# Strain-Maxim.net
KiCad netlist of a schematic drawn in Altium Designer
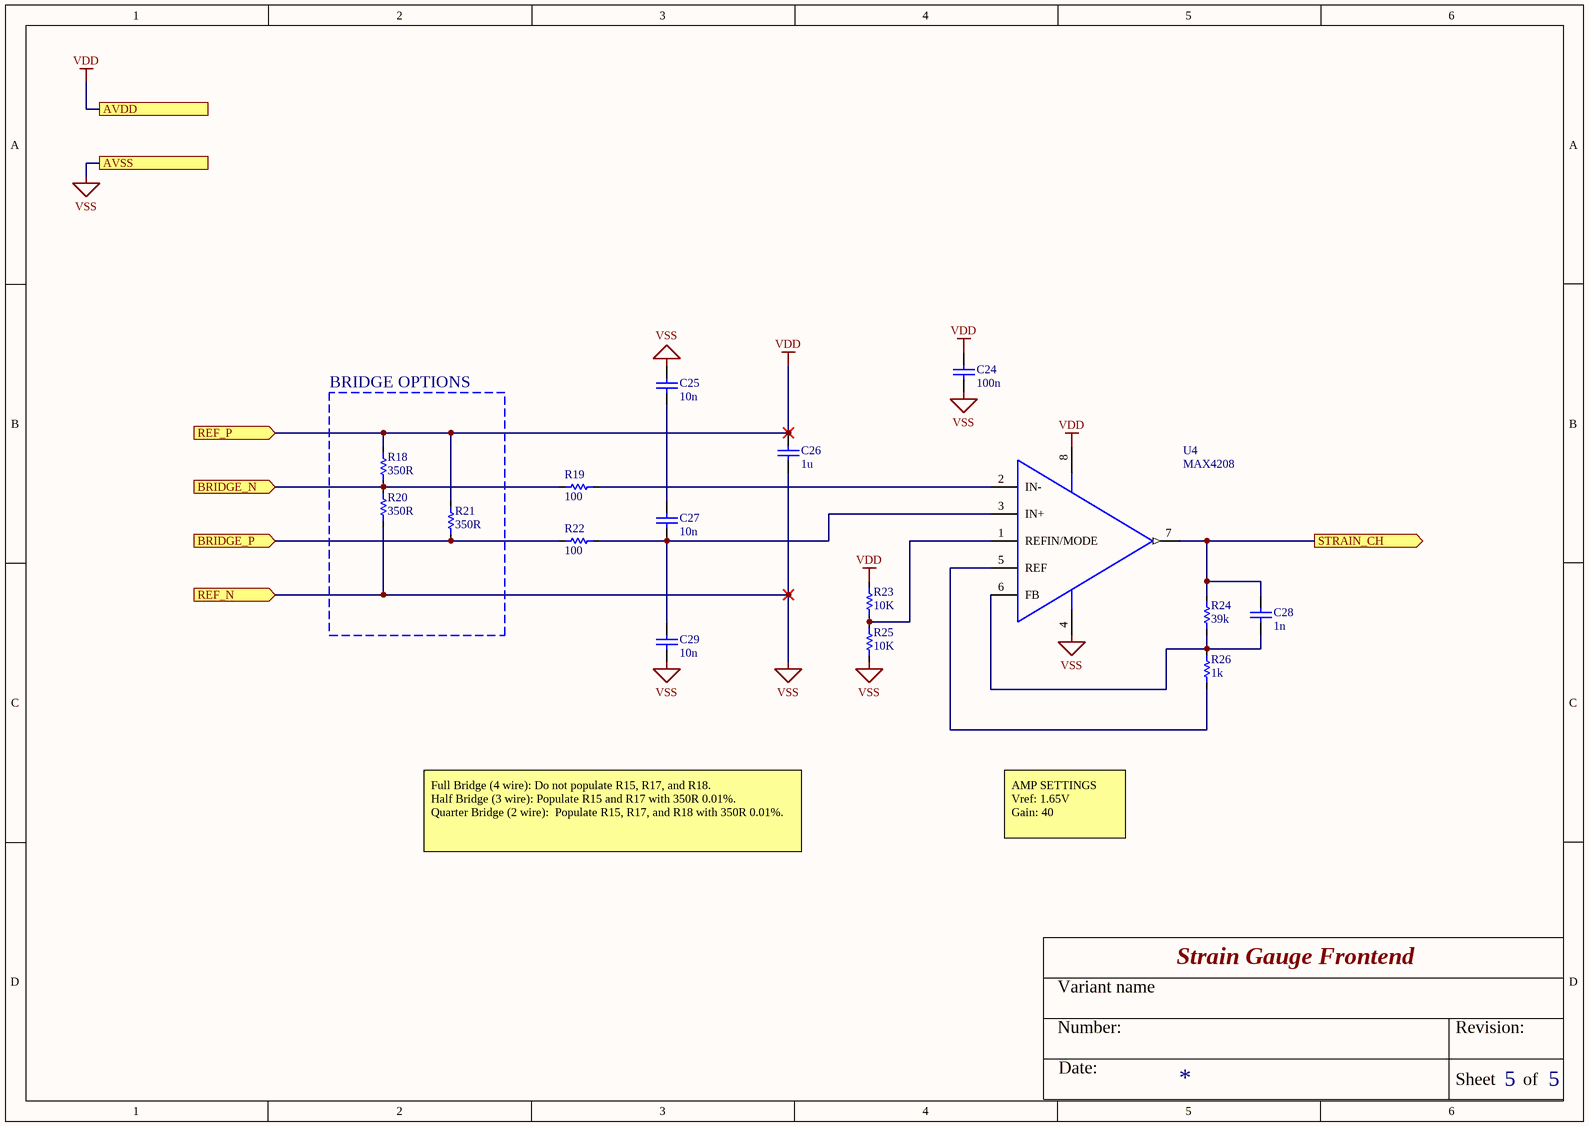
[diagram p0: Strain-Maxim.SchDoc]

(export (version "E")
  (design (tool "Eeschema 10.0.6"))
  (components
    (comp (ref "C24")
      (value "100n")
      (footprint "CAP_0603_M")
      (description "CAP Cnom Vcap Ptol Dial 0603")
      (fields (field (name "CREATED BY") "JS"))
      (libsource (lib "Passives") (part "CAP_0603"))
    )
    (comp (ref "C25")
      (value "10n")
      (footprint "CAP_0603_M")
      (description "CAP Cnom Vcap Ptol Dial 0603")
      (fields (field (name "CREATED BY") "JS"))
      (libsource (lib "Passives") (part "CAP_0603"))
    )
    (comp (ref "C26")
      (value "1u")
      (footprint "CAP_0603_M")
      (description "CAP Cnom Vcap Ptol Dial 0603")
      (fields (field (name "CREATED BY") "JS"))
      (libsource (lib "Passives") (part "CAP_0603"))
    )
    (comp (ref "C27")
      (value "10n")
      (footprint "CAP_0603_M")
      (description "CAP Cnom Vcap Ptol Dial 0603")
      (fields (field (name "CREATED BY") "JS"))
      (libsource (lib "Passives") (part "CAP_0603"))
    )
    (comp (ref "C28")
      (value "1n")
      (footprint "CAP_0603_M")
      (description "CAP Cnom Vcap Ptol Dial 0603")
      (fields (field (name "CREATED BY") "JS"))
      (libsource (lib "Passives") (part "CAP_0603"))
    )
    (comp (ref "C29")
      (value "10n")
      (footprint "CAP_0603_M")
      (description "CAP Cnom Vcap Ptol Dial 0603")
      (fields (field (name "CREATED BY") "JS"))
      (libsource (lib "Passives") (part "CAP_0603"))
    )
    (comp (ref "R18")
      (value "350R")
      (footprint "RES_0603_M")
      (description "RES OPT 1/5W 0603")
      (fields (field (name "CREATED BY") "JS"))
      (libsource (lib "Passives") (part "RES_0603"))
    )
    (comp (ref "R19")
      (value "100")
      (footprint "RES_0603_M")
      (description "RES OPT 1/5W 0603")
      (fields (field (name "CREATED BY") "JS"))
      (libsource (lib "Passives") (part "RES_0603"))
    )
    (comp (ref "R20")
      (value "350R")
      (footprint "RES_0603_M")
      (description "RES OPT 1/5W 0603")
      (fields (field (name "CREATED BY") "JS"))
      (libsource (lib "Passives") (part "RES_0603"))
    )
    (comp (ref "R21")
      (value "350R")
      (footprint "RES_0603_M")
      (description "RES OPT 1/5W 0603")
      (fields (field (name "CREATED BY") "JS"))
      (libsource (lib "Passives") (part "RES_0603"))
    )
    (comp (ref "R22")
      (value "100")
      (footprint "RES_0603_M")
      (description "RES OPT 1/5W 0603")
      (fields (field (name "CREATED BY") "JS"))
      (libsource (lib "Passives") (part "RES_0603"))
    )
    (comp (ref "R23")
      (value "10K")
      (footprint "RES_0603_M")
      (description "RES OPT 1/5W 0603")
      (fields (field (name "CREATED BY") "JS"))
      (libsource (lib "Passives") (part "RES_0603"))
    )
    (comp (ref "R24")
      (value "39k")
      (footprint "RES_0603_M")
      (description "RES OPT 1/5W 0603")
      (fields (field (name "CREATED BY") "JS"))
      (libsource (lib "Passives") (part "RES_0603"))
    )
    (comp (ref "R25")
      (value "10K")
      (footprint "RES_0603_M")
      (description "RES OPT 1/5W 0603")
      (fields (field (name "CREATED BY") "JS"))
      (libsource (lib "Passives") (part "RES_0603"))
    )
    (comp (ref "R26")
      (value "1k")
      (footprint "RES_0603_M")
      (description "RES OPT 1/5W 0603")
      (fields (field (name "CREATED BY") "JS"))
      (libsource (lib "Passives") (part "RES_0603"))
    )
    (comp (ref "U4")
      (value "MAX4208")
      (footprint "MAX4208_SOP127P600-8N")
      (fields (field (name "MANUFACTURER") "Maxim"))
      (libsource (lib "IC") (part "MAX4208"))
    )
  )
  (nets
    (net (code "1") (name "/BRIDGE_N") (class "Default")
      (node (ref "R18") (pin "1") (pinfunction "1_1") (pintype "passive"))
      (node (ref "R19") (pin "1") (pinfunction "1_1") (pintype "passive"))
      (node (ref "R20") (pin "2") (pinfunction "2_2") (pintype "passive"))
    )
    (net (code "2") (name "/BRIDGE_P") (class "Default")
      (node (ref "R21") (pin "1") (pinfunction "1_1") (pintype "passive"))
      (node (ref "R22") (pin "1") (pinfunction "1_1") (pintype "passive"))
    )
    (net (code "3") (name "/STRAIN_CH") (class "Default")
      (node (ref "C28") (pin "2") (pinfunction "2_2") (pintype "passive"))
      (node (ref "R24") (pin "2") (pinfunction "2_2") (pintype "passive"))
      (node (ref "U4") (pin "7") (pinfunction "VO_7") (pintype "output"))
    )
    (net (code "4") (name "Net-(C25-Pad1)") (class "Default")
      (node (ref "C25") (pin "1") (pinfunction "1_1") (pintype "passive"))
      (node (ref "C27") (pin "2") (pinfunction "2_2") (pintype "passive"))
    )
    (net (code "5") (name "Net-(U4-FB)") (class "Default")
      (node (ref "C28") (pin "1") (pinfunction "1_1") (pintype "passive"))
      (node (ref "R24") (pin "1") (pinfunction "1_1") (pintype "passive"))
      (node (ref "R26") (pin "2") (pinfunction "2_2") (pintype "passive"))
      (node (ref "U4") (pin "6") (pinfunction "FB_6") (pintype "passive"))
    )
    (net (code "6") (name "Net-(U4-IN+)") (class "Default")
      (node (ref "C27") (pin "1") (pinfunction "1_1") (pintype "passive"))
      (node (ref "C29") (pin "2") (pinfunction "2_2") (pintype "passive"))
      (node (ref "R22") (pin "2") (pinfunction "2_2") (pintype "passive"))
      (node (ref "U4") (pin "3") (pinfunction "IN+_3") (pintype "passive"))
    )
    (net (code "7") (name "Net-(U4-IN-)") (class "Default")
      (node (ref "R19") (pin "2") (pinfunction "2_2") (pintype "passive"))
      (node (ref "U4") (pin "2") (pinfunction "IN-_2") (pintype "passive"))
    )
    (net (code "8") (name "Net-(U4-REF)") (class "Default")
      (node (ref "R26") (pin "1") (pinfunction "1_1") (pintype "passive"))
      (node (ref "U4") (pin "5") (pinfunction "REF_5") (pintype "passive"))
    )
    (net (code "9") (name "Net-(U4-REFIN{slash}MODE)") (class "Default")
      (node (ref "R23") (pin "1") (pinfunction "1_1") (pintype "passive"))
      (node (ref "R25") (pin "2") (pinfunction "2_2") (pintype "passive"))
      (node (ref "U4") (pin "1") (pinfunction "REFIN/MODE_1") (pintype "passive"))
    )
    (net (code "10") (name "VDD") (class "Default")
      (node (ref "C24") (pin "2") (pinfunction "2_2") (pintype "passive"))
      (node (ref "C26") (pin "2") (pinfunction "2_2") (pintype "passive"))
      (node (ref "R18") (pin "2") (pinfunction "2_2") (pintype "passive"))
      (node (ref "R21") (pin "2") (pinfunction "2_2") (pintype "passive"))
      (node (ref "R23") (pin "2") (pinfunction "2_2") (pintype "passive"))
      (node (ref "U4") (pin "8") (pinfunction "V+_8") (pintype "power_in"))
    )
    (net (code "11") (name "VSS") (class "Default")
      (node (ref "C24") (pin "1") (pinfunction "1_1") (pintype "passive"))
      (node (ref "C25") (pin "2") (pinfunction "2_2") (pintype "passive"))
      (node (ref "C26") (pin "1") (pinfunction "1_1") (pintype "passive"))
      (node (ref "C29") (pin "1") (pinfunction "1_1") (pintype "passive"))
      (node (ref "R20") (pin "1") (pinfunction "1_1") (pintype "passive"))
      (node (ref "R25") (pin "1") (pinfunction "1_1") (pintype "passive"))
      (node (ref "U4") (pin "4") (pinfunction "V-_4") (pintype "power_in"))
    )
  )
)
